# ZHSD-DDR3L.net
KiCad netlist of a schematic drawn in Altium Designer
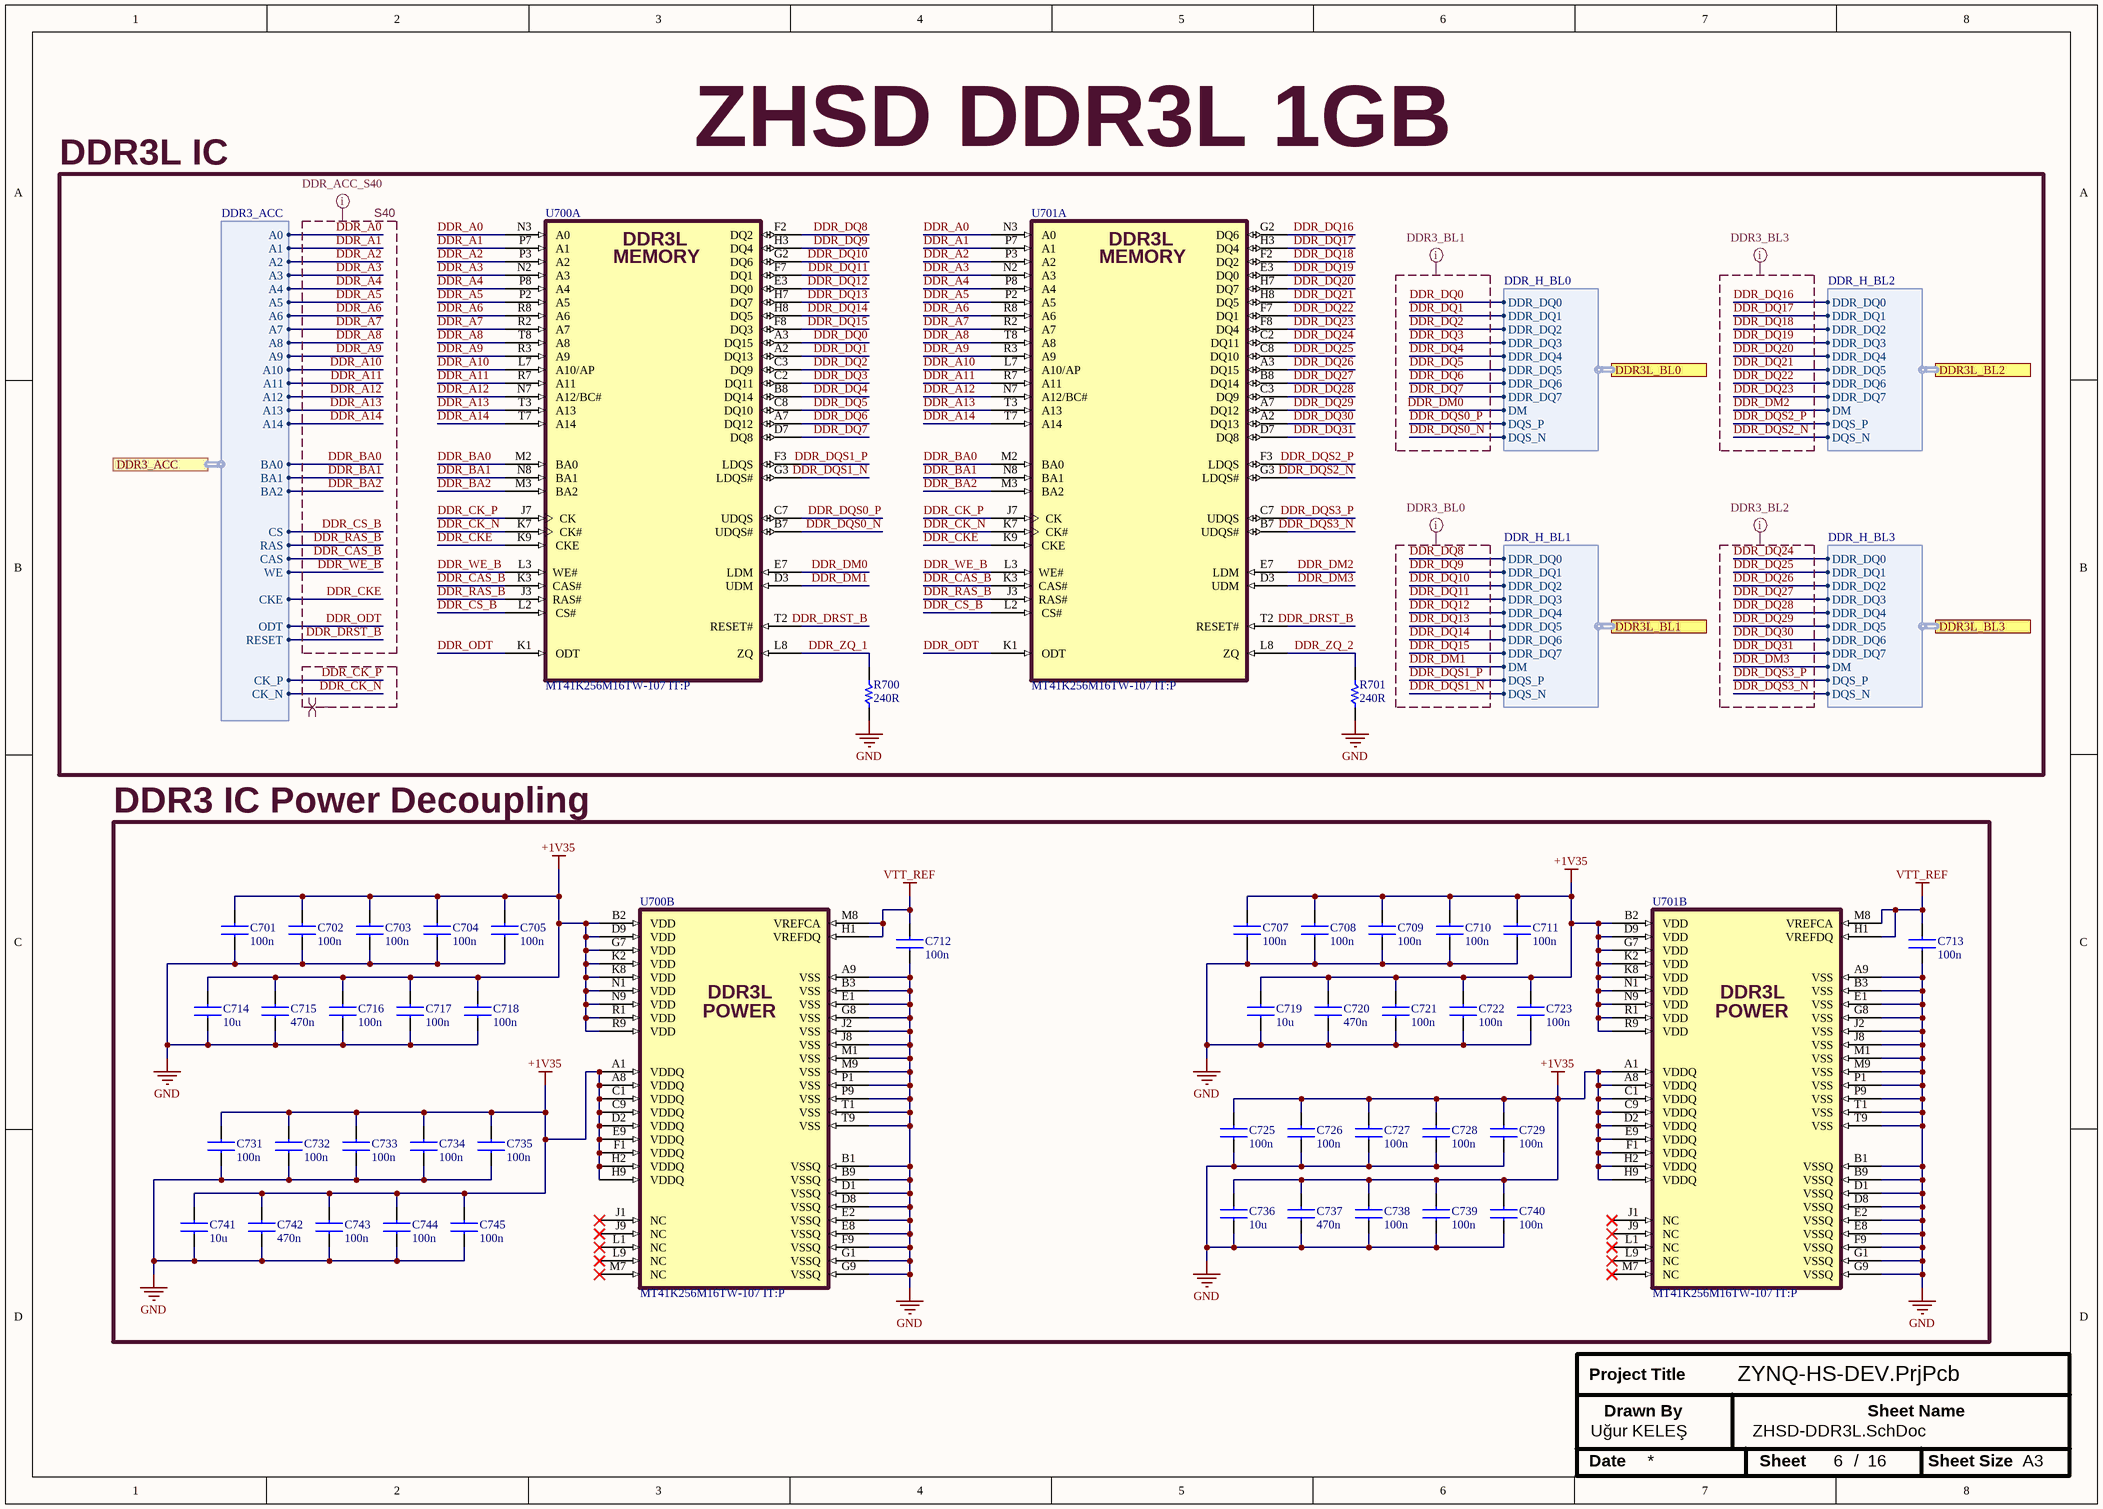
[diagram p0: ZHSD-DDR3L.SchDoc]

(export (version "E")
  (design (tool "Eeschema 10.0.6"))
  (components
    (comp (ref "C701")
      (value "100n")
      (footprint "0402CAPC1005X06N")
      (description "CAP CER 0.1UF 16V X7R 0402 (1005) ±10%")
      (fields (field (name "MANUFACTURER") "Murata Electronics") (field (name "MPN") "GRM155R71C104KA88J"))
      (libsource (lib "UK_Library_SCH") (part "GRM155R71C104KA88J"))
    )
    (comp (ref "C702")
      (value "100n")
      (footprint "0402CAPC1005X06N")
      (description "CAP CER 0.1UF 16V X7R 0402 (1005) ±10%")
      (fields (field (name "MANUFACTURER") "Murata Electronics") (field (name "MPN") "GRM155R71C104KA88J"))
      (libsource (lib "UK_Library_SCH") (part "GRM155R71C104KA88J"))
    )
    (comp (ref "C703")
      (value "100n")
      (footprint "0402CAPC1005X06N")
      (description "CAP CER 0.1UF 16V X7R 0402 (1005) ±10%")
      (fields (field (name "MANUFACTURER") "Murata Electronics") (field (name "MPN") "GRM155R71C104KA88J"))
      (libsource (lib "UK_Library_SCH") (part "GRM155R71C104KA88J"))
    )
    (comp (ref "C704")
      (value "100n")
      (footprint "0402CAPC1005X06N")
      (description "CAP CER 0.1UF 16V X7R 0402 (1005) ±10%")
      (fields (field (name "MANUFACTURER") "Murata Electronics") (field (name "MPN") "GRM155R71C104KA88J"))
      (libsource (lib "UK_Library_SCH") (part "GRM155R71C104KA88J"))
    )
    (comp (ref "C705")
      (value "100n")
      (footprint "0402CAPC1005X06N")
      (description "CAP CER 0.1UF 16V X7R 0402 (1005) ±10%")
      (fields (field (name "MANUFACTURER") "Murata Electronics") (field (name "MPN") "GRM155R71C104KA88J"))
      (libsource (lib "UK_Library_SCH") (part "GRM155R71C104KA88J"))
    )
    (comp (ref "C707")
      (value "100n")
      (footprint "0402CAPC1005X06N")
      (description "CAP CER 0.1UF 16V X7R 0402 (1005) ±10%")
      (fields (field (name "MANUFACTURER") "Murata Electronics") (field (name "MPN") "GRM155R71C104KA88J"))
      (libsource (lib "UK_Library_SCH") (part "GRM155R71C104KA88J"))
    )
    (comp (ref "C708")
      (value "100n")
      (footprint "0402CAPC1005X06N")
      (description "CAP CER 0.1UF 16V X7R 0402 (1005) ±10%")
      (fields (field (name "MANUFACTURER") "Murata Electronics") (field (name "MPN") "GRM155R71C104KA88J"))
      (libsource (lib "UK_Library_SCH") (part "GRM155R71C104KA88J"))
    )
    (comp (ref "C709")
      (value "100n")
      (footprint "0402CAPC1005X06N")
      (description "CAP CER 0.1UF 16V X7R 0402 (1005) ±10%")
      (fields (field (name "MANUFACTURER") "Murata Electronics") (field (name "MPN") "GRM155R71C104KA88J"))
      (libsource (lib "UK_Library_SCH") (part "GRM155R71C104KA88J"))
    )
    (comp (ref "C710")
      (value "100n")
      (footprint "0402CAPC1005X06N")
      (description "CAP CER 0.1UF 16V X7R 0402 (1005) ±10%")
      (fields (field (name "MANUFACTURER") "Murata Electronics") (field (name "MPN") "GRM155R71C104KA88J"))
      (libsource (lib "UK_Library_SCH") (part "GRM155R71C104KA88J"))
    )
    (comp (ref "C711")
      (value "100n")
      (footprint "0402CAPC1005X06N")
      (description "CAP CER 0.1UF 16V X7R 0402 (1005) ±10%")
      (fields (field (name "MANUFACTURER") "Murata Electronics") (field (name "MPN") "GRM155R71C104KA88J"))
      (libsource (lib "UK_Library_SCH") (part "GRM155R71C104KA88J"))
    )
    (comp (ref "C712")
      (value "100n")
      (footprint "0402CAPC1005X06N")
      (description "CAP CER 0.1UF 16V X7R 0402 (1005) ±10%")
      (fields (field (name "MANUFACTURER") "Murata Electronics") (field (name "MPN") "GRM155R71C104KA88J"))
      (libsource (lib "UK_Library_SCH") (part "GRM155R71C104KA88J"))
    )
    (comp (ref "C713")
      (value "100n")
      (footprint "0402CAPC1005X06N")
      (description "CAP CER 0.1UF 16V X7R 0402 (1005) ±10%")
      (fields (field (name "MANUFACTURER") "Murata Electronics") (field (name "MPN") "GRM155R71C104KA88J"))
      (libsource (lib "UK_Library_SCH") (part "GRM155R71C104KA88J"))
    )
    (comp (ref "C714")
      (value "10u")
      (footprint "0603CAPC1608X09N")
      (description "CAP CER 10UF 10V X7R 0603 (1608) ±20%")
      (fields (field (name "MANUFACTURER") "Murata Electronics") (field (name "MPN") "GRM188Z71A106MA73D"))
      (libsource (lib "UK_Library") (part "GRM188Z71A106MA73D"))
    )
    (comp (ref "C715")
      (value "470n")
      (footprint "0402CAPC1005X06N")
      (description "CAP CER 0.47UF 6.3V X5R 0402(1005) ±10%")
      (fields (field (name "MANUFACTURER") "Murata Electronics") (field (name "MPN") "GRM155R60J474KE19D"))
      (libsource (lib "UK_Library") (part "GRM155R60J474KE19D"))
    )
    (comp (ref "C716")
      (value "100n")
      (footprint "0402CAPC1005X06N")
      (description "CAP CER 0.1UF 16V X7R 0402 (1005) ±10%")
      (fields (field (name "MANUFACTURER") "Murata Electronics") (field (name "MPN") "GRM155R71C104KA88J"))
      (libsource (lib "UK_Library_SCH") (part "GRM155R71C104KA88J"))
    )
    (comp (ref "C717")
      (value "100n")
      (footprint "0402CAPC1005X06N")
      (description "CAP CER 0.1UF 16V X7R 0402 (1005) ±10%")
      (fields (field (name "MANUFACTURER") "Murata Electronics") (field (name "MPN") "GRM155R71C104KA88J"))
      (libsource (lib "UK_Library_SCH") (part "GRM155R71C104KA88J"))
    )
    (comp (ref "C718")
      (value "100n")
      (footprint "0402CAPC1005X06N")
      (description "CAP CER 0.1UF 16V X7R 0402 (1005) ±10%")
      (fields (field (name "MANUFACTURER") "Murata Electronics") (field (name "MPN") "GRM155R71C104KA88J"))
      (libsource (lib "UK_Library_SCH") (part "GRM155R71C104KA88J"))
    )
    (comp (ref "C719")
      (value "10u")
      (footprint "0603CAPC1608X09N")
      (description "CAP CER 10UF 10V X7R 0603 (1608) ±20%")
      (fields (field (name "MANUFACTURER") "Murata Electronics") (field (name "MPN") "GRM188Z71A106MA73D"))
      (libsource (lib "UK_Library") (part "GRM188Z71A106MA73D"))
    )
    (comp (ref "C720")
      (value "470n")
      (footprint "0402CAPC1005X06N")
      (description "CAP CER 0.47UF 6.3V X5R 0402(1005) ±10%")
      (fields (field (name "MANUFACTURER") "Murata Electronics") (field (name "MPN") "GRM155R60J474KE19D"))
      (libsource (lib "UK_Library") (part "GRM155R60J474KE19D"))
    )
    (comp (ref "C721")
      (value "100n")
      (footprint "0402CAPC1005X06N")
      (description "CAP CER 0.1UF 16V X7R 0402 (1005) ±10%")
      (fields (field (name "MANUFACTURER") "Murata Electronics") (field (name "MPN") "GRM155R71C104KA88J"))
      (libsource (lib "UK_Library_SCH") (part "GRM155R71C104KA88J"))
    )
    (comp (ref "C722")
      (value "100n")
      (footprint "0402CAPC1005X06N")
      (description "CAP CER 0.1UF 16V X7R 0402 (1005) ±10%")
      (fields (field (name "MANUFACTURER") "Murata Electronics") (field (name "MPN") "GRM155R71C104KA88J"))
      (libsource (lib "UK_Library_SCH") (part "GRM155R71C104KA88J"))
    )
    (comp (ref "C723")
      (value "100n")
      (footprint "0402CAPC1005X06N")
      (description "CAP CER 0.1UF 16V X7R 0402 (1005) ±10%")
      (fields (field (name "MANUFACTURER") "Murata Electronics") (field (name "MPN") "GRM155R71C104KA88J"))
      (libsource (lib "UK_Library_SCH") (part "GRM155R71C104KA88J"))
    )
    (comp (ref "C725")
      (value "100n")
      (footprint "0402CAPC1005X06N")
      (description "CAP CER 0.1UF 16V X7R 0402 (1005) ±10%")
      (fields (field (name "MANUFACTURER") "Murata Electronics") (field (name "MPN") "GRM155R71C104KA88J"))
      (libsource (lib "UK_Library_SCH") (part "GRM155R71C104KA88J"))
    )
    (comp (ref "C726")
      (value "100n")
      (footprint "0402CAPC1005X06N")
      (description "CAP CER 0.1UF 16V X7R 0402 (1005) ±10%")
      (fields (field (name "MANUFACTURER") "Murata Electronics") (field (name "MPN") "GRM155R71C104KA88J"))
      (libsource (lib "UK_Library_SCH") (part "GRM155R71C104KA88J"))
    )
    (comp (ref "C727")
      (value "100n")
      (footprint "0402CAPC1005X06N")
      (description "CAP CER 0.1UF 16V X7R 0402 (1005) ±10%")
      (fields (field (name "MANUFACTURER") "Murata Electronics") (field (name "MPN") "GRM155R71C104KA88J"))
      (libsource (lib "UK_Library_SCH") (part "GRM155R71C104KA88J"))
    )
    (comp (ref "C728")
      (value "100n")
      (footprint "0402CAPC1005X06N")
      (description "CAP CER 0.1UF 16V X7R 0402 (1005) ±10%")
      (fields (field (name "MANUFACTURER") "Murata Electronics") (field (name "MPN") "GRM155R71C104KA88J"))
      (libsource (lib "UK_Library_SCH") (part "GRM155R71C104KA88J"))
    )
    (comp (ref "C729")
      (value "100n")
      (footprint "0402CAPC1005X06N")
      (description "CAP CER 0.1UF 16V X7R 0402 (1005) ±10%")
      (fields (field (name "MANUFACTURER") "Murata Electronics") (field (name "MPN") "GRM155R71C104KA88J"))
      (libsource (lib "UK_Library_SCH") (part "GRM155R71C104KA88J"))
    )
    (comp (ref "C731")
      (value "100n")
      (footprint "0402CAPC1005X06N")
      (description "CAP CER 0.1UF 16V X7R 0402 (1005) ±10%")
      (fields (field (name "MANUFACTURER") "Murata Electronics") (field (name "MPN") "GRM155R71C104KA88J"))
      (libsource (lib "UK_Library_SCH") (part "GRM155R71C104KA88J"))
    )
    (comp (ref "C732")
      (value "100n")
      (footprint "0402CAPC1005X06N")
      (description "CAP CER 0.1UF 16V X7R 0402 (1005) ±10%")
      (fields (field (name "MANUFACTURER") "Murata Electronics") (field (name "MPN") "GRM155R71C104KA88J"))
      (libsource (lib "UK_Library_SCH") (part "GRM155R71C104KA88J"))
    )
    (comp (ref "C733")
      (value "100n")
      (footprint "0402CAPC1005X06N")
      (description "CAP CER 0.1UF 16V X7R 0402 (1005) ±10%")
      (fields (field (name "MANUFACTURER") "Murata Electronics") (field (name "MPN") "GRM155R71C104KA88J"))
      (libsource (lib "UK_Library_SCH") (part "GRM155R71C104KA88J"))
    )
    (comp (ref "C734")
      (value "100n")
      (footprint "0402CAPC1005X06N")
      (description "CAP CER 0.1UF 16V X7R 0402 (1005) ±10%")
      (fields (field (name "MANUFACTURER") "Murata Electronics") (field (name "MPN") "GRM155R71C104KA88J"))
      (libsource (lib "UK_Library_SCH") (part "GRM155R71C104KA88J"))
    )
    (comp (ref "C735")
      (value "100n")
      (footprint "0402CAPC1005X06N")
      (description "CAP CER 0.1UF 16V X7R 0402 (1005) ±10%")
      (fields (field (name "MANUFACTURER") "Murata Electronics") (field (name "MPN") "GRM155R71C104KA88J"))
      (libsource (lib "UK_Library_SCH") (part "GRM155R71C104KA88J"))
    )
    (comp (ref "C736")
      (value "10u")
      (footprint "0603CAPC1608X09N")
      (description "CAP CER 10UF 10V X7R 0603 (1608) ±20%")
      (fields (field (name "MANUFACTURER") "Murata Electronics") (field (name "MPN") "GRM188Z71A106MA73D"))
      (libsource (lib "UK_Library") (part "GRM188Z71A106MA73D"))
    )
    (comp (ref "C737")
      (value "470n")
      (footprint "0402CAPC1005X06N")
      (description "CAP CER 0.47UF 6.3V X5R 0402(1005) ±10%")
      (fields (field (name "MANUFACTURER") "Murata Electronics") (field (name "MPN") "GRM155R60J474KE19D"))
      (libsource (lib "UK_Library") (part "GRM155R60J474KE19D"))
    )
    (comp (ref "C738")
      (value "100n")
      (footprint "0402CAPC1005X06N")
      (description "CAP CER 0.1UF 16V X7R 0402 (1005) ±10%")
      (fields (field (name "MANUFACTURER") "Murata Electronics") (field (name "MPN") "GRM155R71C104KA88J"))
      (libsource (lib "UK_Library_SCH") (part "GRM155R71C104KA88J"))
    )
    (comp (ref "C739")
      (value "100n")
      (footprint "0402CAPC1005X06N")
      (description "CAP CER 0.1UF 16V X7R 0402 (1005) ±10%")
      (fields (field (name "MANUFACTURER") "Murata Electronics") (field (name "MPN") "GRM155R71C104KA88J"))
      (libsource (lib "UK_Library_SCH") (part "GRM155R71C104KA88J"))
    )
    (comp (ref "C740")
      (value "100n")
      (footprint "0402CAPC1005X06N")
      (description "CAP CER 0.1UF 16V X7R 0402 (1005) ±10%")
      (fields (field (name "MANUFACTURER") "Murata Electronics") (field (name "MPN") "GRM155R71C104KA88J"))
      (libsource (lib "UK_Library_SCH") (part "GRM155R71C104KA88J"))
    )
    (comp (ref "C741")
      (value "10u")
      (footprint "0603CAPC1608X09N")
      (description "CAP CER 10UF 10V X7R 0603 (1608) ±20%")
      (fields (field (name "MANUFACTURER") "Murata Electronics") (field (name "MPN") "GRM188Z71A106MA73D"))
      (libsource (lib "UK_Library") (part "GRM188Z71A106MA73D"))
    )
    (comp (ref "C742")
      (value "470n")
      (footprint "0402CAPC1005X06N")
      (description "CAP CER 0.47UF 6.3V X5R 0402(1005) ±10%")
      (fields (field (name "MANUFACTURER") "Murata Electronics") (field (name "MPN") "GRM155R60J474KE19D"))
      (libsource (lib "UK_Library") (part "GRM155R60J474KE19D"))
    )
    (comp (ref "C743")
      (value "100n")
      (footprint "0402CAPC1005X06N")
      (description "CAP CER 0.1UF 16V X7R 0402 (1005) ±10%")
      (fields (field (name "MANUFACTURER") "Murata Electronics") (field (name "MPN") "GRM155R71C104KA88J"))
      (libsource (lib "UK_Library_SCH") (part "GRM155R71C104KA88J"))
    )
    (comp (ref "C744")
      (value "100n")
      (footprint "0402CAPC1005X06N")
      (description "CAP CER 0.1UF 16V X7R 0402 (1005) ±10%")
      (fields (field (name "MANUFACTURER") "Murata Electronics") (field (name "MPN") "GRM155R71C104KA88J"))
      (libsource (lib "UK_Library_SCH") (part "GRM155R71C104KA88J"))
    )
    (comp (ref "C745")
      (value "100n")
      (footprint "0402CAPC1005X06N")
      (description "CAP CER 0.1UF 16V X7R 0402 (1005) ±10%")
      (fields (field (name "MANUFACTURER") "Murata Electronics") (field (name "MPN") "GRM155R71C104KA88J"))
      (libsource (lib "UK_Library_SCH") (part "GRM155R71C104KA88J"))
    )
    (comp (ref "R700")
      (value "240R")
      (footprint "0402RESC1005X04N")
      (description "RES 240 OHM 1% 1/16W 0402 (1005)")
      (fields (field (name "MANUFACTURER") "YAGEO") (field (name "MPN") "RC0402FR-07240RL"))
      (libsource (lib "UK_Library") (part "RC0402FR-07240RL"))
    )
    (comp (ref "R701")
      (value "240R")
      (footprint "0402RESC1005X04N")
      (description "RES 240 OHM 1% 1/16W 0402 (1005)")
      (fields (field (name "MANUFACTURER") "YAGEO") (field (name "MPN") "RC0402FR-07240RL"))
      (libsource (lib "UK_Library") (part "RC0402FR-07240RL"))
    )
    (comp (ref "U700")
      (value "MT41K256M16TW-107 IT:P")
      (footprint "BGA96C80P9X16_900X1400X110")
      (description "SDRAM - DDR3L Memory IC 4Gbit Parallel 933 MHz 20 ns 96-FBGA (8x14)")
      (fields (field (name "MANUFACTURER") "Micron Technology Inc."))
      (libsource (lib "") (part "MT41K256M16TW-107 IT{colon}P_1"))
    )
    (comp (ref "U701")
      (value "MT41K256M16TW-107 IT:P")
      (footprint "BGA96C80P9X16_900X1400X110")
      (description "SDRAM - DDR3L Memory IC 4Gbit Parallel 933 MHz 20 ns 96-FBGA (8x14)")
      (fields (field (name "MANUFACTURER") "Micron Technology Inc."))
      (libsource (lib "") (part "MT41K256M16TW-107 IT{colon}P_2"))
    )
  )
  (nets
    (net (code "6") (name "+1V35") (class "Default")
      (node (ref "C701") (pin "2") (pinfunction "2_2") (pintype "passive"))
      (node (ref "C702") (pin "2") (pinfunction "2_2") (pintype "passive"))
      (node (ref "C703") (pin "2") (pinfunction "2_2") (pintype "passive"))
      (node (ref "C704") (pin "2") (pinfunction "2_2") (pintype "passive"))
      (node (ref "C705") (pin "2") (pinfunction "2_2") (pintype "passive"))
      (node (ref "C707") (pin "2") (pinfunction "2_2") (pintype "passive"))
      (node (ref "C708") (pin "2") (pinfunction "2_2") (pintype "passive"))
      (node (ref "C709") (pin "2") (pinfunction "2_2") (pintype "passive"))
      (node (ref "C710") (pin "2") (pinfunction "2_2") (pintype "passive"))
      (node (ref "C711") (pin "2") (pinfunction "2_2") (pintype "passive"))
      (node (ref "C714") (pin "2") (pinfunction "2_2") (pintype "passive"))
      (node (ref "C715") (pin "2") (pinfunction "2_2") (pintype "passive"))
      (node (ref "C716") (pin "2") (pinfunction "2_2") (pintype "passive"))
      (node (ref "C717") (pin "2") (pinfunction "2_2") (pintype "passive"))
      (node (ref "C718") (pin "2") (pinfunction "2_2") (pintype "passive"))
      (node (ref "C719") (pin "2") (pinfunction "2_2") (pintype "passive"))
      (node (ref "C720") (pin "2") (pinfunction "2_2") (pintype "passive"))
      (node (ref "C721") (pin "2") (pinfunction "2_2") (pintype "passive"))
      (node (ref "C722") (pin "2") (pinfunction "2_2") (pintype "passive"))
      (node (ref "C723") (pin "2") (pinfunction "2_2") (pintype "passive"))
      (node (ref "C725") (pin "2") (pinfunction "2_2") (pintype "passive"))
      (node (ref "C726") (pin "2") (pinfunction "2_2") (pintype "passive"))
      (node (ref "C727") (pin "2") (pinfunction "2_2") (pintype "passive"))
      (node (ref "C728") (pin "2") (pinfunction "2_2") (pintype "passive"))
      (node (ref "C729") (pin "2") (pinfunction "2_2") (pintype "passive"))
      (node (ref "C731") (pin "2") (pinfunction "2_2") (pintype "passive"))
      (node (ref "C732") (pin "2") (pinfunction "2_2") (pintype "passive"))
      (node (ref "C733") (pin "2") (pinfunction "2_2") (pintype "passive"))
      (node (ref "C734") (pin "2") (pinfunction "2_2") (pintype "passive"))
      (node (ref "C735") (pin "2") (pinfunction "2_2") (pintype "passive"))
      (node (ref "C736") (pin "2") (pinfunction "2_2") (pintype "passive"))
      (node (ref "C737") (pin "2") (pinfunction "2_2") (pintype "passive"))
      (node (ref "C738") (pin "2") (pinfunction "2_2") (pintype "passive"))
      (node (ref "C739") (pin "2") (pinfunction "2_2") (pintype "passive"))
      (node (ref "C740") (pin "2") (pinfunction "2_2") (pintype "passive"))
      (node (ref "C741") (pin "2") (pinfunction "2_2") (pintype "passive"))
      (node (ref "C742") (pin "2") (pinfunction "2_2") (pintype "passive"))
      (node (ref "C743") (pin "2") (pinfunction "2_2") (pintype "passive"))
      (node (ref "C744") (pin "2") (pinfunction "2_2") (pintype "passive"))
      (node (ref "C745") (pin "2") (pinfunction "2_2") (pintype "passive"))
      (node (ref "U700") (pin "A1") (pinfunction "_VDDQ_A1") (pintype "input"))
      (node (ref "U700") (pin "A8") (pinfunction "_VDDQ_A8") (pintype "input"))
      (node (ref "U700") (pin "B2") (pinfunction "_VDD_B2") (pintype "input"))
      (node (ref "U700") (pin "C1") (pinfunction "_VDDQ_C1") (pintype "input"))
      (node (ref "U700") (pin "C9") (pinfunction "_VDDQ_C9") (pintype "input"))
      (node (ref "U700") (pin "D2") (pinfunction "_VDDQ_D2") (pintype "input"))
      (node (ref "U700") (pin "D9") (pinfunction "_VDD_D9") (pintype "input"))
      (node (ref "U700") (pin "E9") (pinfunction "_VDDQ_E9") (pintype "input"))
      (node (ref "U700") (pin "F1") (pinfunction "_VDDQ_F1") (pintype "input"))
      (node (ref "U700") (pin "G7") (pinfunction "_VDD_G7") (pintype "input"))
      (node (ref "U700") (pin "H2") (pinfunction "_VDDQ_H2") (pintype "input"))
      (node (ref "U700") (pin "H9") (pinfunction "_VDDQ_H9") (pintype "input"))
      (node (ref "U700") (pin "K2") (pinfunction "_VDD_K2") (pintype "input"))
      (node (ref "U700") (pin "K8") (pinfunction "_VDD_K8") (pintype "input"))
      (node (ref "U700") (pin "N1") (pinfunction "_VDD_N1") (pintype "input"))
      (node (ref "U700") (pin "N9") (pinfunction "_VDD_N9") (pintype "input"))
      (node (ref "U700") (pin "R1") (pinfunction "_VDD_R1") (pintype "input"))
      (node (ref "U700") (pin "R9") (pinfunction "_VDD_R9") (pintype "input"))
      (node (ref "U701") (pin "A1") (pinfunction "_VDDQ_A1") (pintype "input"))
      (node (ref "U701") (pin "A8") (pinfunction "_VDDQ_A8") (pintype "input"))
      (node (ref "U701") (pin "B2") (pinfunction "_VDD_B2") (pintype "input"))
      (node (ref "U701") (pin "C1") (pinfunction "_VDDQ_C1") (pintype "input"))
      (node (ref "U701") (pin "C9") (pinfunction "_VDDQ_C9") (pintype "input"))
      (node (ref "U701") (pin "D2") (pinfunction "_VDDQ_D2") (pintype "input"))
      (node (ref "U701") (pin "D9") (pinfunction "_VDD_D9") (pintype "input"))
      (node (ref "U701") (pin "E9") (pinfunction "_VDDQ_E9") (pintype "input"))
      (node (ref "U701") (pin "F1") (pinfunction "_VDDQ_F1") (pintype "input"))
      (node (ref "U701") (pin "G7") (pinfunction "_VDD_G7") (pintype "input"))
      (node (ref "U701") (pin "H2") (pinfunction "_VDDQ_H2") (pintype "input"))
      (node (ref "U701") (pin "H9") (pinfunction "_VDDQ_H9") (pintype "input"))
      (node (ref "U701") (pin "K2") (pinfunction "_VDD_K2") (pintype "input"))
      (node (ref "U701") (pin "K8") (pinfunction "_VDD_K8") (pintype "input"))
      (node (ref "U701") (pin "N1") (pinfunction "_VDD_N1") (pintype "input"))
      (node (ref "U701") (pin "N9") (pinfunction "_VDD_N9") (pintype "input"))
      (node (ref "U701") (pin "R1") (pinfunction "_VDD_R1") (pintype "input"))
      (node (ref "U701") (pin "R9") (pinfunction "_VDD_R9") (pintype "input"))
    )
    (net (code "7") (name "/DDR_A0") (class "Default")
      (node (ref "U700") (pin "N3") (pinfunction "_A0_N3") (pintype "input"))
      (node (ref "U701") (pin "N3") (pinfunction "_A0_N3") (pintype "input"))
    )
    (net (code "8") (name "/DDR_A1") (class "Default")
      (node (ref "U700") (pin "P7") (pinfunction "_A1_P7") (pintype "input"))
      (node (ref "U701") (pin "P7") (pinfunction "_A1_P7") (pintype "input"))
    )
    (net (code "9") (name "/DDR_A2") (class "Default")
      (node (ref "U700") (pin "P3") (pinfunction "_A2_P3") (pintype "input"))
      (node (ref "U701") (pin "P3") (pinfunction "_A2_P3") (pintype "input"))
    )
    (net (code "10") (name "/DDR_A3") (class "Default")
      (node (ref "U700") (pin "N2") (pinfunction "_A3_N2") (pintype "input"))
      (node (ref "U701") (pin "N2") (pinfunction "_A3_N2") (pintype "input"))
    )
    (net (code "11") (name "/DDR_A4") (class "Default")
      (node (ref "U700") (pin "P8") (pinfunction "_A4_P8") (pintype "input"))
      (node (ref "U701") (pin "P8") (pinfunction "_A4_P8") (pintype "input"))
    )
    (net (code "12") (name "/DDR_A5") (class "Default")
      (node (ref "U700") (pin "P2") (pinfunction "_A5_P2") (pintype "input"))
      (node (ref "U701") (pin "P2") (pinfunction "_A5_P2") (pintype "input"))
    )
    (net (code "13") (name "/DDR_A6") (class "Default")
      (node (ref "U700") (pin "R8") (pinfunction "_A6_R8") (pintype "input"))
      (node (ref "U701") (pin "R8") (pinfunction "_A6_R8") (pintype "input"))
    )
    (net (code "14") (name "/DDR_A7") (class "Default")
      (node (ref "U700") (pin "R2") (pinfunction "_A7_R2") (pintype "input"))
      (node (ref "U701") (pin "R2") (pinfunction "_A7_R2") (pintype "input"))
    )
    (net (code "15") (name "/DDR_A8") (class "Default")
      (node (ref "U700") (pin "T8") (pinfunction "_A8_T8") (pintype "input"))
      (node (ref "U701") (pin "T8") (pinfunction "_A8_T8") (pintype "input"))
    )
    (net (code "16") (name "/DDR_A9") (class "Default")
      (node (ref "U700") (pin "R3") (pinfunction "_A9_R3") (pintype "input"))
      (node (ref "U701") (pin "R3") (pinfunction "_A9_R3") (pintype "input"))
    )
    (net (code "17") (name "/DDR_A10") (class "Default")
      (node (ref "U700") (pin "L7") (pinfunction "_A10/AP_L7") (pintype "input"))
      (node (ref "U701") (pin "L7") (pinfunction "_A10/AP_L7") (pintype "input"))
    )
    (net (code "18") (name "/DDR_A11") (class "Default")
      (node (ref "U700") (pin "R7") (pinfunction "_A11_R7") (pintype "input"))
      (node (ref "U701") (pin "R7") (pinfunction "_A11_R7") (pintype "input"))
    )
    (net (code "19") (name "/DDR_A12") (class "Default")
      (node (ref "U700") (pin "N7") (pinfunction "_A12/BC#_N7") (pintype "input"))
      (node (ref "U701") (pin "N7") (pinfunction "_A12/BC#_N7") (pintype "input"))
    )
    (net (code "20") (name "/DDR_A13") (class "Default")
      (node (ref "U700") (pin "T3") (pinfunction "_A13_T3") (pintype "input"))
      (node (ref "U701") (pin "T3") (pinfunction "_A13_T3") (pintype "input"))
    )
    (net (code "21") (name "/DDR_A14") (class "Default")
      (node (ref "U700") (pin "T7") (pinfunction "_A14_T7") (pintype "input"))
      (node (ref "U701") (pin "T7") (pinfunction "_A14_T7") (pintype "input"))
    )
    (net (code "22") (name "/DDR_BA0") (class "Default")
      (node (ref "U700") (pin "M2") (pinfunction "_BA0_M2") (pintype "input"))
      (node (ref "U701") (pin "M2") (pinfunction "_BA0_M2") (pintype "input"))
    )
    (net (code "23") (name "/DDR_BA1") (class "Default")
      (node (ref "U700") (pin "N8") (pinfunction "_BA1_N8") (pintype "input"))
      (node (ref "U701") (pin "N8") (pinfunction "_BA1_N8") (pintype "input"))
    )
    (net (code "24") (name "/DDR_BA2") (class "Default")
      (node (ref "U700") (pin "M3") (pinfunction "_BA2_M3") (pintype "input"))
      (node (ref "U701") (pin "M3") (pinfunction "_BA2_M3") (pintype "input"))
    )
    (net (code "25") (name "/DDR_CAS_B") (class "Default")
      (node (ref "U700") (pin "K3") (pinfunction "CAS#_K3") (pintype "input"))
      (node (ref "U701") (pin "K3") (pinfunction "CAS#_K3") (pintype "input"))
    )
    (net (code "26") (name "/DDR_CKE") (class "Default")
      (node (ref "U700") (pin "K9") (pinfunction "_CKE_K9") (pintype "input"))
      (node (ref "U701") (pin "K9") (pinfunction "_CKE_K9") (pintype "input"))
    )
    (net (code "27") (name "/DDR_CK_N") (class "Default")
      (node (ref "U700") (pin "K7") (pinfunction "_CK#_K7") (pintype "input"))
      (node (ref "U701") (pin "K7") (pinfunction "_CK#_K7") (pintype "input"))
    )
    (net (code "28") (name "/DDR_CK_P") (class "Default")
      (node (ref "U700") (pin "J7") (pinfunction "_CK_J7") (pintype "input"))
      (node (ref "U701") (pin "J7") (pinfunction "_CK_J7") (pintype "input"))
    )
    (net (code "29") (name "/DDR_CS_B") (class "Default")
      (node (ref "U700") (pin "L2") (pinfunction "_CS#_L2") (pintype "input"))
      (node (ref "U701") (pin "L2") (pinfunction "_CS#_L2") (pintype "input"))
    )
    (net (code "30") (name "/DDR_DM0") (class "Default")
      (node (ref "U700") (pin "E7") (pinfunction "_LDM_E7") (pintype "input"))
    )
    (net (code "31") (name "/DDR_DM1") (class "Default")
      (node (ref "U700") (pin "D3") (pinfunction "_UDM_D3") (pintype "input"))
    )
    (net (code "32") (name "/DDR_DM2") (class "Default")
      (node (ref "U701") (pin "E7") (pinfunction "_LDM_E7") (pintype "input"))
    )
    (net (code "33") (name "/DDR_DM3") (class "Default")
      (node (ref "U701") (pin "D3") (pinfunction "_UDM_D3") (pintype "input"))
    )
    (net (code "34") (name "/DDR_DQ0") (class "Default")
      (node (ref "U700") (pin "A3") (pinfunction "_DQ15_A3") (pintype "bidirectional"))
    )
    (net (code "35") (name "/DDR_DQ1") (class "Default")
      (node (ref "U700") (pin "A2") (pinfunction "_DQ13_A2") (pintype "bidirectional"))
    )
    (net (code "36") (name "/DDR_DQ2") (class "Default")
      (node (ref "U700") (pin "C3") (pinfunction "_DQ9_C3") (pintype "bidirectional"))
    )
    (net (code "37") (name "/DDR_DQ3") (class "Default")
      (node (ref "U700") (pin "C2") (pinfunction "_DQ11_C2") (pintype "bidirectional"))
    )
    (net (code "38") (name "/DDR_DQ4") (class "Default")
      (node (ref "U700") (pin "B8") (pinfunction "_DQ14_B8") (pintype "bidirectional"))
    )
    (net (code "39") (name "/DDR_DQ5") (class "Default")
      (node (ref "U700") (pin "C8") (pinfunction "_DQ10_C8") (pintype "bidirectional"))
    )
    (net (code "40") (name "/DDR_DQ6") (class "Default")
      (node (ref "U700") (pin "A7") (pinfunction "_DQ12_A7") (pintype "bidirectional"))
    )
    (net (code "41") (name "/DDR_DQ7") (class "Default")
      (node (ref "U700") (pin "D7") (pinfunction "_DQ8_D7") (pintype "bidirectional"))
    )
    (net (code "42") (name "/DDR_DQ8") (class "Default")
      (node (ref "U700") (pin "F2") (pinfunction "_DQ2_F2") (pintype "bidirectional"))
    )
    (net (code "43") (name "/DDR_DQ9") (class "Default")
      (node (ref "U700") (pin "H3") (pinfunction "_DQ4_H3") (pintype "bidirectional"))
    )
    (net (code "44") (name "/DDR_DQ10") (class "Default")
      (node (ref "U700") (pin "G2") (pinfunction "_DQ6_G2") (pintype "bidirectional"))
    )
    (net (code "45") (name "/DDR_DQ11") (class "Default")
      (node (ref "U700") (pin "F7") (pinfunction "_DQ1_F7") (pintype "bidirectional"))
    )
    (net (code "46") (name "/DDR_DQ12") (class "Default")
      (node (ref "U700") (pin "E3") (pinfunction "_DQ0_E3") (pintype "bidirectional"))
    )
    (net (code "47") (name "/DDR_DQ13") (class "Default")
      (node (ref "U700") (pin "H7") (pinfunction "_DQ7_H7") (pintype "bidirectional"))
    )
    (net (code "48") (name "/DDR_DQ14") (class "Default")
      (node (ref "U700") (pin "H8") (pinfunction "_DQ5_H8") (pintype "bidirectional"))
    )
    (net (code "49") (name "/DDR_DQ15") (class "Default")
      (node (ref "U700") (pin "F8") (pinfunction "_DQ3_F8") (pintype "bidirectional"))
    )
    (net (code "50") (name "/DDR_DQ16") (class "Default")
      (node (ref "U701") (pin "G2") (pinfunction "_DQ6_G2") (pintype "bidirectional"))
    )
    (net (code "51") (name "/DDR_DQ17") (class "Default")
      (node (ref "U701") (pin "H3") (pinfunction "_DQ4_H3") (pintype "bidirectional"))
    )
    (net (code "52") (name "/DDR_DQ18") (class "Default")
      (node (ref "U701") (pin "F2") (pinfunction "_DQ2_F2") (pintype "bidirectional"))
    )
    (net (code "53") (name "/DDR_DQ19") (class "Default")
      (node (ref "U701") (pin "E3") (pinfunction "_DQ0_E3") (pintype "bidirectional"))
    )
    (net (code "54") (name "/DDR_DQ20") (class "Default")
      (node (ref "U701") (pin "H7") (pinfunction "_DQ7_H7") (pintype "bidirectional"))
    )
    (net (code "55") (name "/DDR_DQ21") (class "Default")
      (node (ref "U701") (pin "H8") (pinfunction "_DQ5_H8") (pintype "bidirectional"))
    )
    (net (code "56") (name "/DDR_DQ22") (class "Default")
      (node (ref "U701") (pin "F7") (pinfunction "_DQ1_F7") (pintype "bidirectional"))
    )
    (net (code "57") (name "/DDR_DQ23") (class "Default")
      (node (ref "U701") (pin "F8") (pinfunction "_DQ4_F8") (pintype "bidirectional"))
    )
    (net (code "58") (name "/DDR_DQ24") (class "Default")
      (node (ref "U701") (pin "C2") (pinfunction "_DQ11_C2") (pintype "bidirectional"))
    )
    (net (code "59") (name "/DDR_DQ25") (class "Default")
      (node (ref "U701") (pin "C8") (pinfunction "_DQ10_C8") (pintype "bidirectional"))
    )
    (net (code "60") (name "/DDR_DQ26") (class "Default")
      (node (ref "U701") (pin "A3") (pinfunction "_DQ15_A3") (pintype "bidirectional"))
    )
    (net (code "61") (name "/DDR_DQ27") (class "Default")
      (node (ref "U701") (pin "B8") (pinfunction "_DQ14_B8") (pintype "bidirectional"))
    )
    (net (code "62") (name "/DDR_DQ28") (class "Default")
      (node (ref "U701") (pin "C3") (pinfunction "_DQ9_C3") (pintype "bidirectional"))
    )
    (net (code "63") (name "/DDR_DQ29") (class "Default")
      (node (ref "U701") (pin "A7") (pinfunction "_DQ12_A7") (pintype "bidirectional"))
    )
    (net (code "64") (name "/DDR_DQ30") (class "Default")
      (node (ref "U701") (pin "A2") (pinfunction "_DQ13_A2") (pintype "bidirectional"))
    )
    (net (code "65") (name "/DDR_DQ31") (class "Default")
      (node (ref "U701") (pin "D7") (pinfunction "_DQ8_D7") (pintype "bidirectional"))
    )
    (net (code "66") (name "/DDR_DQS0_N") (class "Default")
      (node (ref "U700") (pin "B7") (pinfunction "_UDQS#_B7") (pintype "bidirectional"))
    )
    (net (code "67") (name "/DDR_DQS0_P") (class "Default")
      (node (ref "U700") (pin "C7") (pinfunction "_UDQS_C7") (pintype "bidirectional"))
    )
    (net (code "68") (name "/DDR_DQS1_N") (class "Default")
      (node (ref "U700") (pin "G3") (pinfunction "_LDQS#_G3") (pintype "bidirectional"))
    )
    (net (code "69") (name "/DDR_DQS1_P") (class "Default")
      (node (ref "U700") (pin "F3") (pinfunction "_LDQS_F3") (pintype "bidirectional"))
    )
    (net (code "70") (name "/DDR_DQS2_N") (class "Default")
      (node (ref "U701") (pin "G3") (pinfunction "_LDQS#_G3") (pintype "bidirectional"))
    )
    (net (code "71") (name "/DDR_DQS2_P") (class "Default")
      (node (ref "U701") (pin "F3") (pinfunction "_LDQS_F3") (pintype "bidirectional"))
    )
    (net (code "72") (name "/DDR_DQS3_N") (class "Default")
      (node (ref "U701") (pin "B7") (pinfunction "_UDQS#_B7") (pintype "bidirectional"))
    )
    (net (code "73") (name "/DDR_DQS3_P") (class "Default")
      (node (ref "U701") (pin "C7") (pinfunction "_UDQS_C7") (pintype "bidirectional"))
    )
    (net (code "74") (name "/DDR_DRST_B") (class "Default")
      (node (ref "U700") (pin "T2") (pinfunction "_RESET#_T2") (pintype "input"))
      (node (ref "U701") (pin "T2") (pinfunction "_RESET#_T2") (pintype "input"))
    )
    (net (code "75") (name "/DDR_ODT") (class "Default")
      (node (ref "U700") (pin "K1") (pinfunction "_ODT_K1") (pintype "input"))
      (node (ref "U701") (pin "K1") (pinfunction "_ODT_K1") (pintype "input"))
    )
    (net (code "76") (name "/DDR_RAS_B") (class "Default")
      (node (ref "U700") (pin "J3") (pinfunction "RAS#_J3") (pintype "input"))
      (node (ref "U701") (pin "J3") (pinfunction "RAS#_J3") (pintype "input"))
    )
    (net (code "77") (name "/DDR_WE_B") (class "Default")
      (node (ref "U700") (pin "L3") (pinfunction "WE#_L3") (pintype "input"))
      (node (ref "U701") (pin "L3") (pinfunction "WE#_L3") (pintype "input"))
    )
    (net (code "78") (name "/DDR_ZQ_1") (class "Default")
      (node (ref "R700") (pin "2") (pinfunction "2_2") (pintype "passive"))
      (node (ref "U700") (pin "L8") (pinfunction "ZQ_L8") (pintype "input"))
    )
    (net (code "79") (name "/DDR_ZQ_2") (class "Default")
      (node (ref "R701") (pin "2") (pinfunction "2_2") (pintype "passive"))
      (node (ref "U701") (pin "L8") (pinfunction "ZQ_L8") (pintype "input"))
    )
    (net (code "85") (name "GND") (class "Default")
      (node (ref "C701") (pin "1") (pinfunction "1_1") (pintype "passive"))
      (node (ref "C702") (pin "1") (pinfunction "1_1") (pintype "passive"))
      (node (ref "C703") (pin "1") (pinfunction "1_1") (pintype "passive"))
      (node (ref "C704") (pin "1") (pinfunction "1_1") (pintype "passive"))
      (node (ref "C705") (pin "1") (pinfunction "1_1") (pintype "passive"))
      (node (ref "C707") (pin "1") (pinfunction "1_1") (pintype "passive"))
      (node (ref "C708") (pin "1") (pinfunction "1_1") (pintype "passive"))
      (node (ref "C709") (pin "1") (pinfunction "1_1") (pintype "passive"))
      (node (ref "C710") (pin "1") (pinfunction "1_1") (pintype "passive"))
      (node (ref "C711") (pin "1") (pinfunction "1_1") (pintype "passive"))
      (node (ref "C712") (pin "1") (pinfunction "1_1") (pintype "passive"))
      (node (ref "C713") (pin "1") (pinfunction "1_1") (pintype "passive"))
      (node (ref "C714") (pin "1") (pinfunction "1_1") (pintype "passive"))
      (node (ref "C715") (pin "1") (pinfunction "1_1") (pintype "passive"))
      (node (ref "C716") (pin "1") (pinfunction "1_1") (pintype "passive"))
      (node (ref "C717") (pin "1") (pinfunction "1_1") (pintype "passive"))
      (node (ref "C718") (pin "1") (pinfunction "1_1") (pintype "passive"))
      (node (ref "C719") (pin "1") (pinfunction "1_1") (pintype "passive"))
      (node (ref "C720") (pin "1") (pinfunction "1_1") (pintype "passive"))
      (node (ref "C721") (pin "1") (pinfunction "1_1") (pintype "passive"))
      (node (ref "C722") (pin "1") (pinfunction "1_1") (pintype "passive"))
      (node (ref "C723") (pin "1") (pinfunction "1_1") (pintype "passive"))
      (node (ref "C725") (pin "1") (pinfunction "1_1") (pintype "passive"))
      (node (ref "C726") (pin "1") (pinfunction "1_1") (pintype "passive"))
      (node (ref "C727") (pin "1") (pinfunction "1_1") (pintype "passive"))
      (node (ref "C728") (pin "1") (pinfunction "1_1") (pintype "passive"))
      (node (ref "C729") (pin "1") (pinfunction "1_1") (pintype "passive"))
      (node (ref "C731") (pin "1") (pinfunction "1_1") (pintype "passive"))
      (node (ref "C732") (pin "1") (pinfunction "1_1") (pintype "passive"))
      (node (ref "C733") (pin "1") (pinfunction "1_1") (pintype "passive"))
      (node (ref "C734") (pin "1") (pinfunction "1_1") (pintype "passive"))
      (node (ref "C735") (pin "1") (pinfunction "1_1") (pintype "passive"))
      (node (ref "C736") (pin "1") (pinfunction "1_1") (pintype "passive"))
      (node (ref "C737") (pin "1") (pinfunction "1_1") (pintype "passive"))
      (node (ref "C738") (pin "1") (pinfunction "1_1") (pintype "passive"))
      (node (ref "C739") (pin "1") (pinfunction "1_1") (pintype "passive"))
      (node (ref "C740") (pin "1") (pinfunction "1_1") (pintype "passive"))
      (node (ref "C741") (pin "1") (pinfunction "1_1") (pintype "passive"))
      (node (ref "C742") (pin "1") (pinfunction "1_1") (pintype "passive"))
      (node (ref "C743") (pin "1") (pinfunction "1_1") (pintype "passive"))
      (node (ref "C744") (pin "1") (pinfunction "1_1") (pintype "passive"))
      (node (ref "C745") (pin "1") (pinfunction "1_1") (pintype "passive"))
      (node (ref "R700") (pin "1") (pinfunction "1_1") (pintype "passive"))
      (node (ref "R701") (pin "1") (pinfunction "1_1") (pintype "passive"))
      (node (ref "U700") (pin "A9") (pinfunction "_VSS_A9") (pintype "input"))
      (node (ref "U700") (pin "B1") (pinfunction "_VSSQ_B1") (pintype "input"))
      (node (ref "U700") (pin "B3") (pinfunction "_VSS_B3") (pintype "input"))
      (node (ref "U700") (pin "B9") (pinfunction "_VSSQ_B9") (pintype "input"))
      (node (ref "U700") (pin "D1") (pinfunction "_VSSQ_D1") (pintype "input"))
      (node (ref "U700") (pin "D8") (pinfunction "_VSSQ_D8") (pintype "input"))
      (node (ref "U700") (pin "E1") (pinfunction "_VSS_E1") (pintype "input"))
      (node (ref "U700") (pin "E2") (pinfunction "_VSSQ_E2") (pintype "input"))
      (node (ref "U700") (pin "E8") (pinfunction "_VSSQ_E8") (pintype "input"))
      (node (ref "U700") (pin "F9") (pinfunction "_VSSQ_F9") (pintype "input"))
      (node (ref "U700") (pin "G1") (pinfunction "_VSSQ_G1") (pintype "input"))
      (node (ref "U700") (pin "G8") (pinfunction "_VSS_G8") (pintype "input"))
      (node (ref "U700") (pin "G9") (pinfunction "_VSSQ_G9") (pintype "input"))
      (node (ref "U700") (pin "J2") (pinfunction "_VSS_J2") (pintype "input"))
      (node (ref "U700") (pin "J8") (pinfunction "_VSS_J8") (pintype "input"))
      (node (ref "U700") (pin "M1") (pinfunction "_VSS_M1") (pintype "input"))
      (node (ref "U700") (pin "M9") (pinfunction "_VSS_M9") (pintype "input"))
      (node (ref "U700") (pin "P1") (pinfunction "_VSS_P1") (pintype "input"))
      (node (ref "U700") (pin "P9") (pinfunction "_VSS_P9") (pintype "input"))
      (node (ref "U700") (pin "T1") (pinfunction "_VSS_T1") (pintype "input"))
      (node (ref "U700") (pin "T9") (pinfunction "_VSS_T9") (pintype "input"))
      (node (ref "U701") (pin "A9") (pinfunction "_VSS_A9") (pintype "input"))
      (node (ref "U701") (pin "B1") (pinfunction "_VSSQ_B1") (pintype "input"))
      (node (ref "U701") (pin "B3") (pinfunction "_VSS_B3") (pintype "input"))
      (node (ref "U701") (pin "B9") (pinfunction "_VSSQ_B9") (pintype "input"))
      (node (ref "U701") (pin "D1") (pinfunction "_VSSQ_D1") (pintype "input"))
      (node (ref "U701") (pin "D8") (pinfunction "_VSSQ_D8") (pintype "input"))
      (node (ref "U701") (pin "E1") (pinfunction "_VSS_E1") (pintype "input"))
      (node (ref "U701") (pin "E2") (pinfunction "_VSSQ_E2") (pintype "input"))
      (node (ref "U701") (pin "E8") (pinfunction "_VSSQ_E8") (pintype "input"))
      (node (ref "U701") (pin "F9") (pinfunction "_VSSQ_F9") (pintype "input"))
      (node (ref "U701") (pin "G1") (pinfunction "_VSSQ_G1") (pintype "input"))
      (node (ref "U701") (pin "G8") (pinfunction "_VSS_G8") (pintype "input"))
      (node (ref "U701") (pin "G9") (pinfunction "_VSSQ_G9") (pintype "input"))
      (node (ref "U701") (pin "J2") (pinfunction "_VSS_J2") (pintype "input"))
      (node (ref "U701") (pin "J8") (pinfunction "_VSS_J8") (pintype "input"))
      (node (ref "U701") (pin "M1") (pinfunction "_VSS_M1") (pintype "input"))
      (node (ref "U701") (pin "M9") (pinfunction "_VSS_M9") (pintype "input"))
      (node (ref "U701") (pin "P1") (pinfunction "_VSS_P1") (pintype "input"))
      (node (ref "U701") (pin "P9") (pinfunction "_VSS_P9") (pintype "input"))
      (node (ref "U701") (pin "T1") (pinfunction "_VSS_T1") (pintype "input"))
      (node (ref "U701") (pin "T9") (pinfunction "_VSS_T9") (pintype "input"))
    )
    (net (code "86") (name "VTT_REF") (class "Default")
      (node (ref "C712") (pin "2") (pinfunction "2_2") (pintype "passive"))
      (node (ref "C713") (pin "2") (pinfunction "2_2") (pintype "passive"))
      (node (ref "U700") (pin "H1") (pinfunction "_VREFDQ_H1") (pintype "input"))
      (node (ref "U700") (pin "M8") (pinfunction "_VREFCA_M8") (pintype "input"))
      (node (ref "U701") (pin "H1") (pinfunction "_VREFDQ_H1") (pintype "input"))
      (node (ref "U701") (pin "M8") (pinfunction "_VREFCA_M8") (pintype "input"))
    )
    (net (code "87") (name "unconnected-(U700B-_NC-PadJ1)") (class "Default")
      (node (ref "U700") (pin "J1") (pinfunction "_NC_J1") (pintype "input+no_connect"))
    )
    (net (code "88") (name "unconnected-(U700B-_NC-PadJ9)") (class "Default")
      (node (ref "U700") (pin "J9") (pinfunction "_NC_J9") (pintype "input+no_connect"))
    )
    (net (code "89") (name "unconnected-(U700B-_NC-PadL1)") (class "Default")
      (node (ref "U700") (pin "L1") (pinfunction "_NC_L1") (pintype "input+no_connect"))
    )
    (net (code "90") (name "unconnected-(U700B-_NC-PadL9)") (class "Default")
      (node (ref "U700") (pin "L9") (pinfunction "_NC_L9") (pintype "input+no_connect"))
    )
    (net (code "91") (name "unconnected-(U700B-_NC-PadM7)") (class "Default")
      (node (ref "U700") (pin "M7") (pinfunction "_NC_M7") (pintype "input+no_connect"))
    )
    (net (code "92") (name "unconnected-(U701B-_NC-PadJ1)") (class "Default")
      (node (ref "U701") (pin "J1") (pinfunction "_NC_J1") (pintype "input+no_connect"))
    )
    (net (code "93") (name "unconnected-(U701B-_NC-PadJ9)") (class "Default")
      (node (ref "U701") (pin "J9") (pinfunction "_NC_J9") (pintype "input+no_connect"))
    )
    (net (code "94") (name "unconnected-(U701B-_NC-PadL1)") (class "Default")
      (node (ref "U701") (pin "L1") (pinfunction "_NC_L1") (pintype "input+no_connect"))
    )
    (net (code "95") (name "unconnected-(U701B-_NC-PadL9)") (class "Default")
      (node (ref "U701") (pin "L9") (pinfunction "_NC_L9") (pintype "input+no_connect"))
    )
    (net (code "96") (name "unconnected-(U701B-_NC-PadM7)") (class "Default")
      (node (ref "U701") (pin "M7") (pinfunction "_NC_M7") (pintype "input+no_connect"))
    )
  )
)
